# RHC12-BTA.net
KiCad netlist of a schematic drawn in Altium Designer
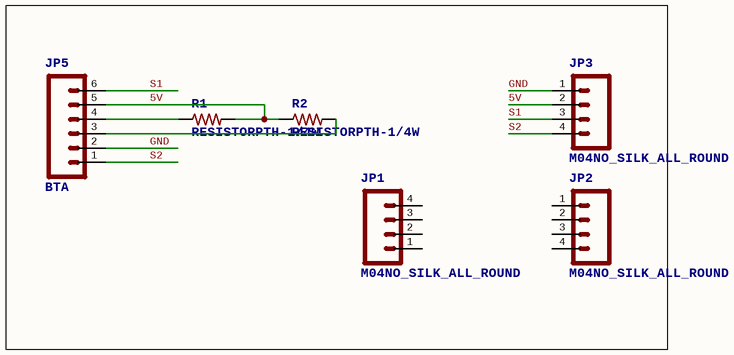
[diagram p0: RHC12-BTA.SchDoc]

(export (version "E")
  (design (tool "Eeschema 10.0.6"))
  (components
    (comp (ref "JP1")
      (value "M04NO_SILK_ALL_ROUND")
      (footprint "1X04_NO_SILK_ALL_ROUND")
      (libsource (lib "SparkFun-Connectors") (part "M04NO_SILK_ALL_ROUND"))
    )
    (comp (ref "JP2")
      (value "M04NO_SILK_ALL_ROUND")
      (footprint "1X04_NO_SILK_ALL_ROUND")
      (libsource (lib "SparkFun-Connectors") (part "M04NO_SILK_ALL_ROUND"))
    )
    (comp (ref "JP3")
      (value "M04NO_SILK_ALL_ROUND")
      (footprint "1X04_NO_SILK_ALL_ROUND")
      (libsource (lib "SparkFun-Connectors") (part "M04NO_SILK_ALL_ROUND"))
    )
    (comp (ref "JP5")
      (value "BTA")
      (footprint "BTA")
      (libsource (lib "SparkFun-Connectors") (part "M06VERNIER-ANALOG"))
    )
    (comp (ref "R1")
      (value "RESISTORPTH-1/4W")
      (footprint "AXIAL-0.4")
      (description "ResistorBasic schematic elements and footprints for 0603, 1206, and PTH resistors.")
      (libsource (lib "SparkFun-Passives") (part "RESISTORPTH-1/4W"))
    )
    (comp (ref "R2")
      (value "RESISTORPTH-1/4W")
      (footprint "AXIAL-0.4")
      (description "ResistorBasic schematic elements and footprints for 0603, 1206, and PTH resistors.")
      (libsource (lib "SparkFun-Passives") (part "RESISTORPTH-1/4W"))
    )
  )
  (nets
    (net (code "1") (name "/5V") (class "Default")
      (node (ref "JP3") (pin "2") (pinfunction "2_2") (pintype "passive"))
      (node (ref "JP5") (pin "5") (pinfunction "5_5") (pintype "passive"))
      (node (ref "R1") (pin "P$2") (pinfunction "2_P$2") (pintype "passive"))
      (node (ref "R2") (pin "P$1") (pinfunction "1_P$1") (pintype "passive"))
    )
    (net (code "2") (name "/GND") (class "Default")
      (node (ref "JP3") (pin "1") (pinfunction "1_1") (pintype "passive"))
      (node (ref "JP5") (pin "2") (pinfunction "2_2") (pintype "passive"))
    )
    (net (code "3") (name "/S1") (class "Default")
      (node (ref "JP3") (pin "3") (pinfunction "3_3") (pintype "passive"))
      (node (ref "JP5") (pin "6") (pinfunction "6_6") (pintype "passive"))
    )
    (net (code "4") (name "/S2") (class "Default")
      (node (ref "JP3") (pin "4") (pinfunction "4_4") (pintype "passive"))
      (node (ref "JP5") (pin "1") (pinfunction "1_1") (pintype "passive"))
    )
    (net (code "5") (name "Net-(R1-1)") (class "Default")
      (node (ref "JP5") (pin "4") (pinfunction "4_4") (pintype "passive"))
      (node (ref "R1") (pin "P$1") (pinfunction "1_P$1") (pintype "passive"))
    )
    (net (code "6") (name "Net-(R2-2)") (class "Default")
      (node (ref "JP5") (pin "3") (pinfunction "3_3") (pintype "passive"))
      (node (ref "R2") (pin "P$2") (pinfunction "2_P$2") (pintype "passive"))
    )
    (net (code "7") (name "unconnected-(JP1-Pad1)") (class "Default")
      (node (ref "JP1") (pin "1") (pinfunction "1_1") (pintype "passive"))
    )
    (net (code "8") (name "unconnected-(JP1-Pad2)") (class "Default")
      (node (ref "JP1") (pin "2") (pinfunction "2_2") (pintype "passive"))
    )
    (net (code "9") (name "unconnected-(JP1-Pad3)") (class "Default")
      (node (ref "JP1") (pin "3") (pinfunction "3_3") (pintype "passive"))
    )
    (net (code "10") (name "unconnected-(JP1-Pad4)") (class "Default")
      (node (ref "JP1") (pin "4") (pinfunction "4_4") (pintype "passive"))
    )
    (net (code "11") (name "unconnected-(JP2-Pad1)") (class "Default")
      (node (ref "JP2") (pin "1") (pinfunction "1_1") (pintype "passive"))
    )
    (net (code "12") (name "unconnected-(JP2-Pad2)") (class "Default")
      (node (ref "JP2") (pin "2") (pinfunction "2_2") (pintype "passive"))
    )
    (net (code "13") (name "unconnected-(JP2-Pad3)") (class "Default")
      (node (ref "JP2") (pin "3") (pinfunction "3_3") (pintype "passive"))
    )
    (net (code "14") (name "unconnected-(JP2-Pad4)") (class "Default")
      (node (ref "JP2") (pin "4") (pinfunction "4_4") (pintype "passive"))
    )
  )
)
